# JBC_Station_V4.net
KiCad netlist of a schematic drawn in EAGLE
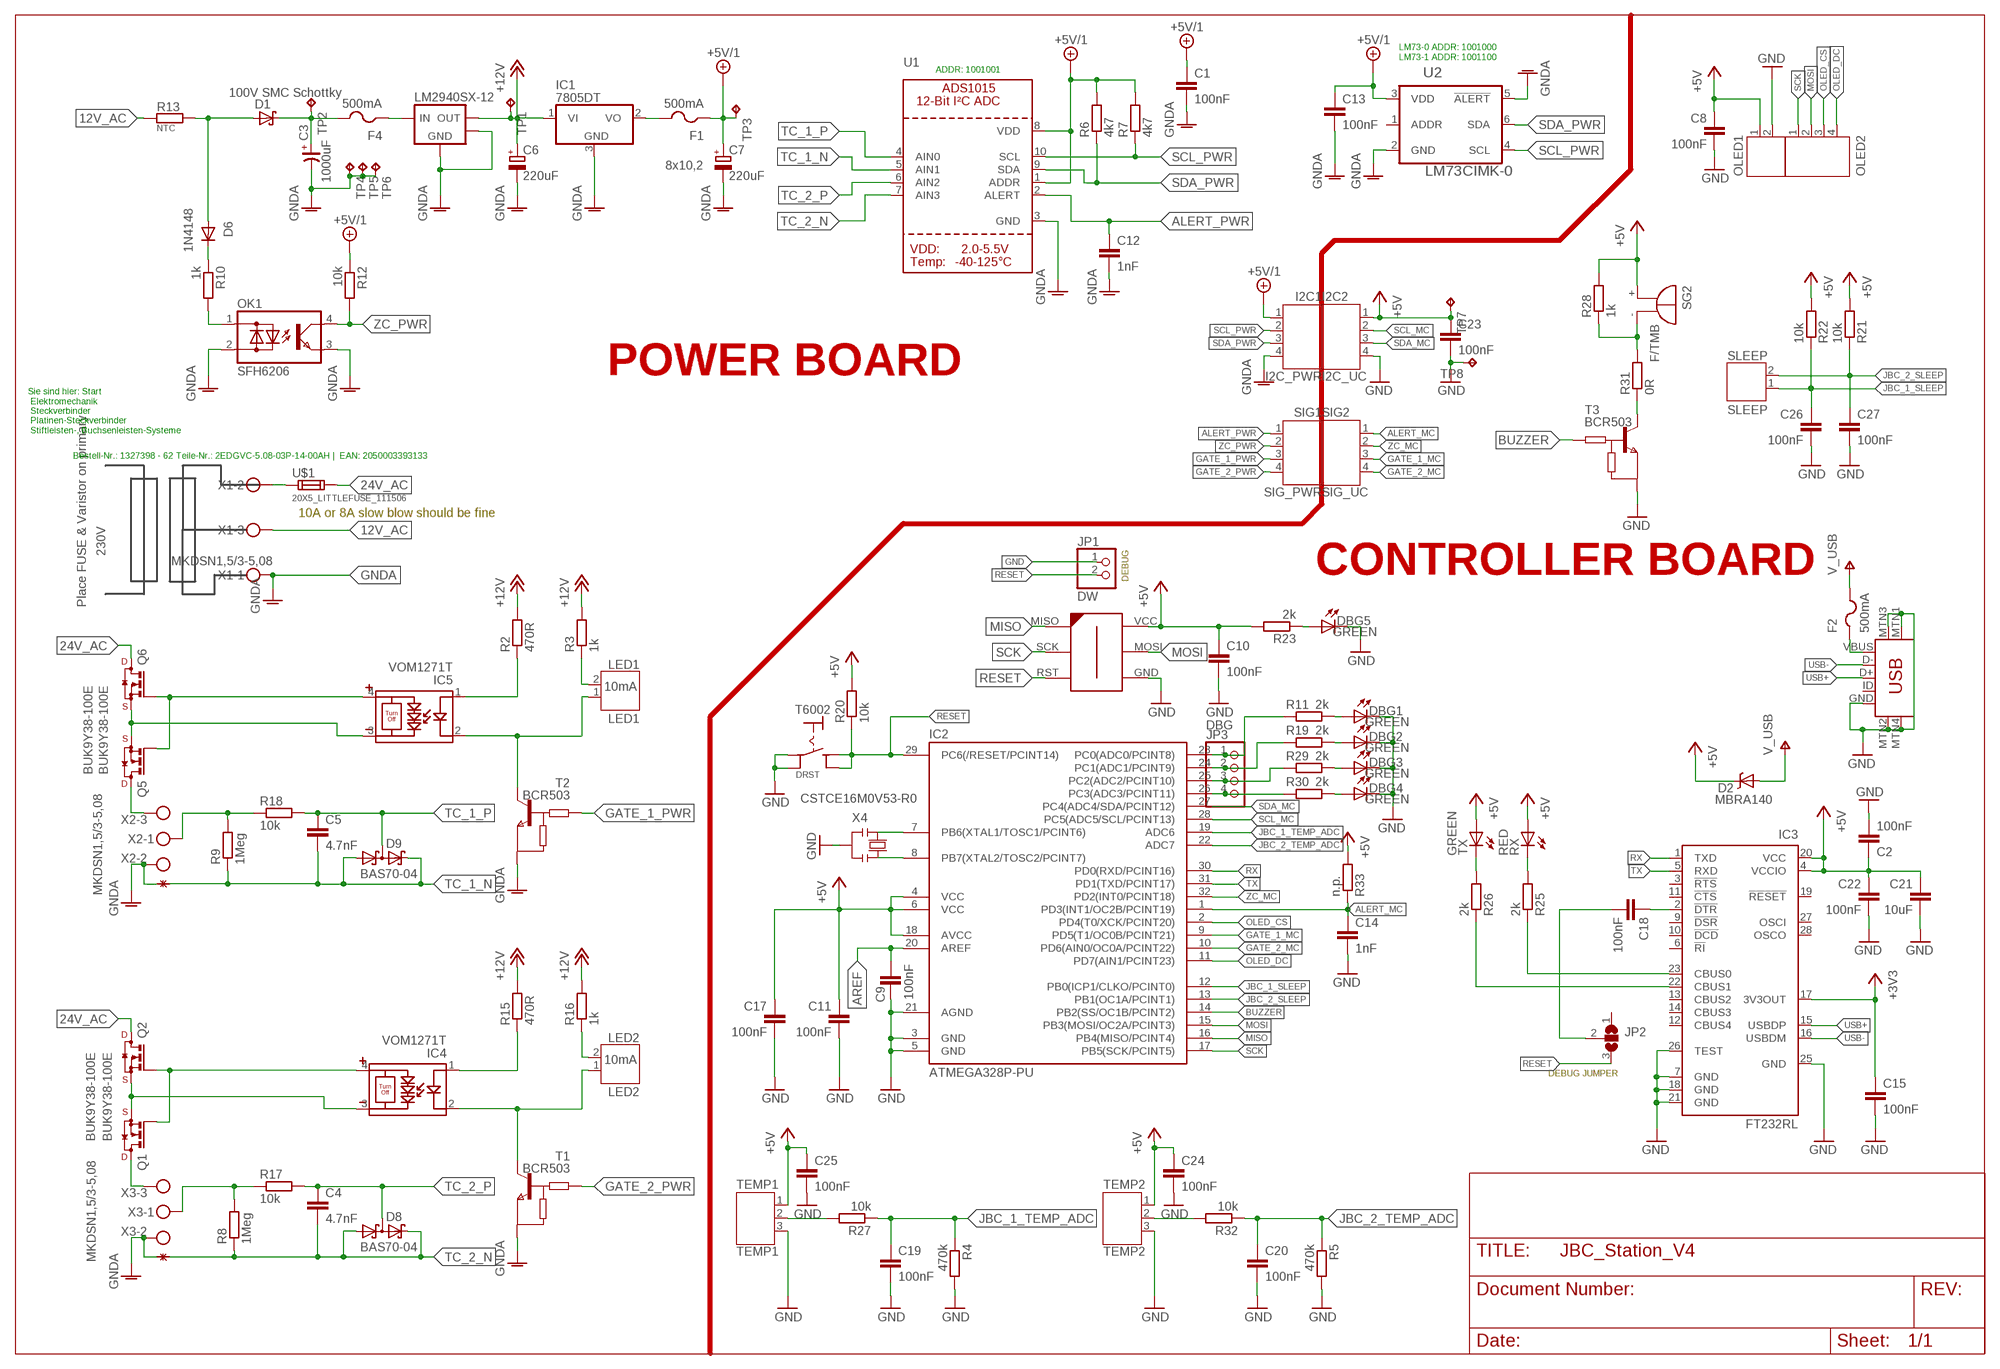
[diagram p0: schematic, sheet 1]

(export (version "E")
  (design (tool "Eeschema 10.0.6"))
  (components
    (comp (ref "C1")
      (value "100nF")
      (footprint "eagle-import:C0805")
      (libsource (lib "eagle-import") (part "C-EUC0805"))
    )
    (comp (ref "C2")
      (value "100nF")
      (footprint "eagle-import:C0805")
      (libsource (lib "eagle-import") (part "C-EUC0805"))
    )
    (comp (ref "C3")
      (value "1000uF")
      (footprint "eagle-import:CSV-H")
      (libsource (lib "eagle-import") (part "CP_SV-H"))
    )
    (comp (ref "C4")
      (value "4.7nF")
      (footprint "eagle-import:C0805")
      (libsource (lib "eagle-import") (part "C-EUC0805"))
    )
    (comp (ref "C5")
      (value "4.7nF")
      (footprint "eagle-import:C0805")
      (libsource (lib "eagle-import") (part "C-EUC0805"))
    )
    (comp (ref "C6")
      (value "220uF")
      (footprint "eagle-import:PANASONIC_E")
      (libsource (lib "eagle-import") (part "CPOL-EUE"))
    )
    (comp (ref "C7")
      (value "220uF")
      (footprint "eagle-import:PANASONIC_E")
      (libsource (lib "eagle-import") (part "CPOL-EUE"))
    )
    (comp (ref "C8")
      (value "100nF")
      (footprint "eagle-import:C0805")
      (libsource (lib "eagle-import") (part "C-EUC0805"))
    )
    (comp (ref "C9")
      (value "100nF")
      (footprint "eagle-import:C0805")
      (libsource (lib "eagle-import") (part "C-EUC0805"))
    )
    (comp (ref "C10")
      (value "100nF")
      (footprint "eagle-import:C0805")
      (libsource (lib "eagle-import") (part "C-EUC0805"))
    )
    (comp (ref "C11")
      (value "100nF")
      (footprint "eagle-import:C0805")
      (libsource (lib "eagle-import") (part "C-EUC0805"))
    )
    (comp (ref "C12")
      (value "1nF")
      (footprint "eagle-import:C0805")
      (libsource (lib "eagle-import") (part "C-EUC0805"))
    )
    (comp (ref "C13")
      (value "100nF")
      (footprint "eagle-import:C0805")
      (libsource (lib "eagle-import") (part "C-EUC0805"))
    )
    (comp (ref "C14")
      (value "1nF")
      (footprint "eagle-import:C0805")
      (libsource (lib "eagle-import") (part "C-EUC0805"))
    )
    (comp (ref "C15")
      (value "100nF")
      (footprint "eagle-import:C0805")
      (libsource (lib "eagle-import") (part "C-EUC0805"))
    )
    (comp (ref "C17")
      (value "100nF")
      (footprint "eagle-import:C0805")
      (libsource (lib "eagle-import") (part "C-EUC0805"))
    )
    (comp (ref "C18")
      (value "100nF")
      (footprint "eagle-import:C0805")
      (libsource (lib "eagle-import") (part "C-EUC0805"))
    )
    (comp (ref "C19")
      (value "100nF")
      (footprint "eagle-import:C0805")
      (libsource (lib "eagle-import") (part "C-EUC0805"))
    )
    (comp (ref "C20")
      (value "100nF")
      (footprint "eagle-import:C0805")
      (libsource (lib "eagle-import") (part "C-EUC0805"))
    )
    (comp (ref "C21")
      (value "10uF")
      (footprint "eagle-import:C1210")
      (libsource (lib "eagle-import") (part "C-EUC1210"))
    )
    (comp (ref "C22")
      (value "100nF")
      (footprint "eagle-import:C0805")
      (libsource (lib "eagle-import") (part "C-EUC0805"))
    )
    (comp (ref "C23")
      (value "100nF")
      (footprint "eagle-import:C0805")
      (libsource (lib "eagle-import") (part "C-EUC0805"))
    )
    (comp (ref "C24")
      (value "100nF")
      (footprint "eagle-import:C0805")
      (libsource (lib "eagle-import") (part "C-EUC0805"))
    )
    (comp (ref "C25")
      (value "100nF")
      (footprint "eagle-import:C0805")
      (libsource (lib "eagle-import") (part "C-EUC0805"))
    )
    (comp (ref "C26")
      (value "100nF")
      (footprint "eagle-import:C0805")
      (libsource (lib "eagle-import") (part "C-EUC0805"))
    )
    (comp (ref "C27")
      (value "100nF")
      (footprint "eagle-import:C0805")
      (libsource (lib "eagle-import") (part "C-EUC0805"))
    )
    (comp (ref "D1")
      (value "100V SMC Schottky")
      (footprint "eagle-import:SMC")
      (libsource (lib "eagle-import") (part "SCHOTTKY-DIODESMC"))
    )
    (comp (ref "D2")
      (value "MBRA140")
      (footprint "eagle-import:SMA-DIODE")
      (libsource (lib "eagle-import") (part "DIODE-SCHOTTKY_"))
    )
    (comp (ref "D6")
      (value "1N4148")
      (footprint "eagle-import:MINIMELF")
      (libsource (lib "eagle-import") (part "DIODE-MINIMELF"))
    )
    (comp (ref "D8")
      (value "BAS70-04")
      (footprint "eagle-import:SOT23")
      (libsource (lib "eagle-import") (part "BAS70-04"))
    )
    (comp (ref "D9")
      (value "BAS70-04")
      (footprint "eagle-import:SOT23")
      (libsource (lib "eagle-import") (part "BAS70-04"))
    )
    (comp (ref "DBG1")
      (value "GREEN")
      (footprint "eagle-import:CHIP-LED0603")
      (libsource (lib "eagle-import") (part "LEDCHIP-LED0603"))
    )
    (comp (ref "DBG2")
      (value "GREEN")
      (footprint "eagle-import:CHIP-LED0603")
      (libsource (lib "eagle-import") (part "LEDCHIP-LED0603"))
    )
    (comp (ref "DBG3")
      (value "GREEN")
      (footprint "eagle-import:CHIP-LED0603")
      (libsource (lib "eagle-import") (part "LEDCHIP-LED0603"))
    )
    (comp (ref "DBG4")
      (value "GREEN")
      (footprint "eagle-import:CHIP-LED0603")
      (libsource (lib "eagle-import") (part "LEDCHIP-LED0603"))
    )
    (comp (ref "DBG5")
      (value "GREEN")
      (footprint "eagle-import:CHIP-LED0603")
      (libsource (lib "eagle-import") (part "LEDCHIP-LED0603"))
    )
    (comp (ref "F1")
      (value "500mA")
      (footprint "eagle-import:R1206")
      (libsource (lib "eagle-import") (part "PTCFUSE-1206"))
    )
    (comp (ref "F2")
      (value "500mA")
      (footprint "eagle-import:R1206")
      (libsource (lib "eagle-import") (part "PTCFUSE-1206"))
    )
    (comp (ref "F4")
      (value "500mA")
      (footprint "eagle-import:R1206")
      (libsource (lib "eagle-import") (part "PTCFUSE-1206"))
    )
    (comp (ref "I2C1")
      (value "I2C_PWR")
      (footprint "eagle-import:JST-PH4")
      (libsource (lib "eagle-import") (part "JST-PH4"))
    )
    (comp (ref "I2C2")
      (value "I2C_UC")
      (footprint "eagle-import:JST-PH4")
      (libsource (lib "eagle-import") (part "JST-PH4"))
    )
    (comp (ref "IC1")
      (value "7805DT")
      (footprint "eagle-import:TO252")
      (libsource (lib "eagle-import") (part "78DT05"))
    )
    (comp (ref "IC2")
      (value "ATMEGA328P-PU")
      (footprint "eagle-import:TQFP32-08")
      (libsource (lib "eagle-import") (part "MEGA48/88/168-AU"))
    )
    (comp (ref "IC3")
      (value "FT232RL")
      (footprint "eagle-import:SSOP28")
      (libsource (lib "eagle-import") (part "FT232RL"))
    )
    (comp (ref "IC4")
      (value "VOM1271T")
      (footprint "eagle-import:SOP-4")
      (libsource (lib "eagle-import") (part "VOM1271T"))
    )
    (comp (ref "IC5")
      (value "VOM1271T")
      (footprint "eagle-import:SOP-4")
      (libsource (lib "eagle-import") (part "VOM1271T"))
    )
    (comp (ref "JP1")
      (value "DW")
      (footprint "eagle-import:1X02")
      (libsource (lib "eagle-import") (part "PINHD-1X2_2.54"))
    )
    (comp (ref "JP2")
      (value "SJ2W")
      (footprint "eagle-import:SJ_2")
      (libsource (lib "eagle-import") (part "SJ2W"))
    )
    (comp (ref "JP3")
      (value "DBG")
      (footprint "eagle-import:1X04_90")
      (libsource (lib "eagle-import") (part "PINHD-1X4/90"))
    )
    (comp (ref "LED1")
      (value "LED1")
      (footprint "eagle-import:JST-PH2")
      (libsource (lib "eagle-import") (part "JST-PH2"))
    )
    (comp (ref "LED2")
      (value "LED2")
      (footprint "eagle-import:JST-PH2")
      (libsource (lib "eagle-import") (part "JST-PH2"))
    )
    (comp (ref "LM2940SX-12")
      (value "LM2940KTT")
      (footprint "eagle-import:TO263-3")
      (libsource (lib "eagle-import") (part "LM2940KTT"))
    )
    (comp (ref "OK1")
      (value "SFH6206")
      (footprint "eagle-import:DIL4-SMD")
      (fields (field (name "MF") "VISHAY/TELEFUNKEN") (field (name "MPN") "SFH6206-3"))
      (libsource (lib "eagle-import") (part "SFH6206"))
    )
    (comp (ref "OLED1")
      (value "JST-PH2")
      (footprint "eagle-import:JST-PH2")
      (libsource (lib "eagle-import") (part "JST-PH2"))
    )
    (comp (ref "OLED2")
      (value "JST-PH4")
      (footprint "eagle-import:JST-PH4")
      (libsource (lib "eagle-import") (part "JST-PH4"))
    )
    (comp (ref "Q1")
      (value "BUK9Y38-100E")
      (footprint "eagle-import:SOT669-POWERPAK-SO-8L-SINGLE")
      (libsource (lib "eagle-import") (part "BUK9Y38-100E"))
    )
    (comp (ref "Q2")
      (value "BUK9Y38-100E")
      (footprint "eagle-import:SOT669-POWERPAK-SO-8L-SINGLE")
      (libsource (lib "eagle-import") (part "BUK9Y38-100E"))
    )
    (comp (ref "Q5")
      (value "BUK9Y38-100E")
      (footprint "eagle-import:SOT669-POWERPAK-SO-8L-SINGLE")
      (libsource (lib "eagle-import") (part "BUK9Y38-100E"))
    )
    (comp (ref "Q6")
      (value "BUK9Y38-100E")
      (footprint "eagle-import:SOT669-POWERPAK-SO-8L-SINGLE")
      (libsource (lib "eagle-import") (part "BUK9Y38-100E"))
    )
    (comp (ref "R2")
      (value "470R")
      (footprint "eagle-import:R0805")
      (libsource (lib "eagle-import") (part "R-EU_R0805"))
    )
    (comp (ref "R3")
      (value "1k")
      (footprint "eagle-import:R0805")
      (libsource (lib "eagle-import") (part "R-EU_R0805"))
    )
    (comp (ref "R4")
      (value "470k")
      (footprint "eagle-import:R0805")
      (libsource (lib "eagle-import") (part "R-EU_R0805"))
    )
    (comp (ref "R5")
      (value "470k")
      (footprint "eagle-import:R0805")
      (libsource (lib "eagle-import") (part "R-EU_R0805"))
    )
    (comp (ref "R6")
      (value "4k7")
      (footprint "eagle-import:R0805")
      (libsource (lib "eagle-import") (part "R-EU_R0805"))
    )
    (comp (ref "R7")
      (value "4k7")
      (footprint "eagle-import:R0805")
      (libsource (lib "eagle-import") (part "R-EU_R0805"))
    )
    (comp (ref "R8")
      (value "1Meg")
      (footprint "eagle-import:R0805")
      (libsource (lib "eagle-import") (part "R-EU_R0805"))
    )
    (comp (ref "R9")
      (value "1Meg")
      (footprint "eagle-import:R0805")
      (libsource (lib "eagle-import") (part "R-EU_R0805"))
    )
    (comp (ref "R10")
      (value "1k")
      (footprint "eagle-import:R0805")
      (libsource (lib "eagle-import") (part "R-EU_R0805"))
    )
    (comp (ref "R11")
      (value "2k")
      (footprint "eagle-import:R0805")
      (libsource (lib "eagle-import") (part "R-EU_R0805"))
    )
    (comp (ref "R12")
      (value "10k")
      (footprint "eagle-import:R0805")
      (libsource (lib "eagle-import") (part "R-EU_R0805"))
    )
    (comp (ref "R13")
      (value "NTC")
      (footprint "eagle-import:SQM-VERTICAL-7W")
      (libsource (lib "eagle-import") (part "SQMR7"))
    )
    (comp (ref "R15")
      (value "470R")
      (footprint "eagle-import:R0805")
      (libsource (lib "eagle-import") (part "R-EU_R0805"))
    )
    (comp (ref "R16")
      (value "1k")
      (footprint "eagle-import:R0805")
      (libsource (lib "eagle-import") (part "R-EU_R0805"))
    )
    (comp (ref "R17")
      (value "10k")
      (footprint "eagle-import:R0805")
      (libsource (lib "eagle-import") (part "R-EU_R0805"))
    )
    (comp (ref "R18")
      (value "10k")
      (footprint "eagle-import:R0805")
      (libsource (lib "eagle-import") (part "R-EU_R0805"))
    )
    (comp (ref "R19")
      (value "2k")
      (footprint "eagle-import:R0805")
      (libsource (lib "eagle-import") (part "R-EU_R0805"))
    )
    (comp (ref "R20")
      (value "10k")
      (footprint "eagle-import:R0805")
      (libsource (lib "eagle-import") (part "R-EU_R0805"))
    )
    (comp (ref "R21")
      (value "10k")
      (footprint "eagle-import:R0805")
      (libsource (lib "eagle-import") (part "R-EU_R0805"))
    )
    (comp (ref "R22")
      (value "10k")
      (footprint "eagle-import:R0805")
      (libsource (lib "eagle-import") (part "R-EU_R0805"))
    )
    (comp (ref "R23")
      (value "2k")
      (footprint "eagle-import:R0805")
      (libsource (lib "eagle-import") (part "R-EU_R0805"))
    )
    (comp (ref "R25")
      (value "2k")
      (footprint "eagle-import:R0805")
      (libsource (lib "eagle-import") (part "R-EU_R0805"))
    )
    (comp (ref "R26")
      (value "2k")
      (footprint "eagle-import:R0805")
      (libsource (lib "eagle-import") (part "R-EU_R0805"))
    )
    (comp (ref "R27")
      (value "10k")
      (footprint "eagle-import:R0805")
      (libsource (lib "eagle-import") (part "R-EU_R0805"))
    )
    (comp (ref "R28")
      (value "1k")
      (footprint "eagle-import:R0805")
      (libsource (lib "eagle-import") (part "R-EU_R0805"))
    )
    (comp (ref "R29")
      (value "2k")
      (footprint "eagle-import:R0805")
      (libsource (lib "eagle-import") (part "R-EU_R0805"))
    )
    (comp (ref "R30")
      (value "2k")
      (footprint "eagle-import:R0805")
      (libsource (lib "eagle-import") (part "R-EU_R0805"))
    )
    (comp (ref "R31")
      (value "0R")
      (footprint "eagle-import:R0805")
      (libsource (lib "eagle-import") (part "R-EU_R0805"))
    )
    (comp (ref "R32")
      (value "10k")
      (footprint "eagle-import:R0805")
      (libsource (lib "eagle-import") (part "R-EU_R0805"))
    )
    (comp (ref "R33")
      (value "n.p.")
      (footprint "eagle-import:R0805")
      (libsource (lib "eagle-import") (part "R-EU_R0805"))
    )
    (comp (ref "RX")
      (value "RED")
      (footprint "eagle-import:CHIP-LED0603")
      (libsource (lib "eagle-import") (part "LEDCHIP-LED0603"))
    )
    (comp (ref "SG2")
      (value "F/TMB")
      (footprint "eagle-import:F_TMB")
      (libsource (lib "eagle-import") (part "F/TMB"))
    )
    (comp (ref "SIG1")
      (value "SIG_PWR")
      (footprint "eagle-import:JST-PH4")
      (libsource (lib "eagle-import") (part "JST-PH4"))
    )
    (comp (ref "SIG2")
      (value "SIG_UC")
      (footprint "eagle-import:JST-PH4")
      (libsource (lib "eagle-import") (part "JST-PH4"))
    )
    (comp (ref "SLEEP")
      (value "SLEEP")
      (footprint "eagle-import:JST-PH2")
      (libsource (lib "eagle-import") (part "JST-PH2"))
    )
    (comp (ref "T1")
      (value "BCR503")
      (footprint "eagle-import:GM4_BIP_SOT23_RZ")
      (libsource (lib "eagle-import") (part "GM4_BIP_NPN-DIG_SOT23_RZ"))
    )
    (comp (ref "T2")
      (value "BCR503")
      (footprint "eagle-import:GM4_BIP_SOT23_RZ")
      (libsource (lib "eagle-import") (part "GM4_BIP_NPN-DIG_SOT23_RZ"))
    )
    (comp (ref "T3")
      (value "BCR503")
      (footprint "eagle-import:GM4_BIP_SOT23_RZ")
      (libsource (lib "eagle-import") (part "GM4_BIP_NPN-DIG_SOT23_RZ"))
    )
    (comp (ref "T6002")
      (value "DRST")
      (footprint "eagle-import:TASTE_DRST_TA1")
      (libsource (lib "eagle-import") (part "TASTE_DRST_TA1"))
    )
    (comp (ref "TEMP1")
      (value "TEMP1")
      (footprint "eagle-import:JST-PH3")
      (libsource (lib "eagle-import") (part "JST-PH3"))
    )
    (comp (ref "TEMP2")
      (value "TEMP2")
      (footprint "eagle-import:JST-PH3")
      (libsource (lib "eagle-import") (part "JST-PH3"))
    )
    (comp (ref "TP1")
      (value "TPTP17R")
      (footprint "eagle-import:TP17R")
      (libsource (lib "eagle-import") (part "TPTP17R"))
    )
    (comp (ref "TP2")
      (value "TPTP17R")
      (footprint "eagle-import:TP17R")
      (libsource (lib "eagle-import") (part "TPTP17R"))
    )
    (comp (ref "TP3")
      (value "TPTP17R")
      (footprint "eagle-import:TP17R")
      (libsource (lib "eagle-import") (part "TPTP17R"))
    )
    (comp (ref "TP4")
      (value "TPTP17R")
      (footprint "eagle-import:TP17R")
      (libsource (lib "eagle-import") (part "TPTP17R"))
    )
    (comp (ref "TP5")
      (value "TPTP17R")
      (footprint "eagle-import:TP17R")
      (libsource (lib "eagle-import") (part "TPTP17R"))
    )
    (comp (ref "TP6")
      (value "TPTP17R")
      (footprint "eagle-import:TP17R")
      (libsource (lib "eagle-import") (part "TPTP17R"))
    )
    (comp (ref "TP7")
      (value "TPTP17R")
      (footprint "eagle-import:TP17R")
      (libsource (lib "eagle-import") (part "TPTP17R"))
    )
    (comp (ref "TP8")
      (value "TPTP17R")
      (footprint "eagle-import:TP17R")
      (libsource (lib "eagle-import") (part "TPTP17R"))
    )
    (comp (ref "TX")
      (value "GREEN")
      (footprint "eagle-import:CHIP-LED0603")
      (libsource (lib "eagle-import") (part "LEDCHIP-LED0603"))
    )
    (comp (ref "U$1")
      (value "20X5_LITTLEFUSE_111506")
      (footprint "eagle-import:20X5_LITTLEFUSE_111506")
      (libsource (lib "eagle-import") (part "20X5_LITTLEFUSE_111506"))
    )
    (comp (ref "U$2")
      (value "STARPONT")
      (footprint "eagle-import:STARPOINT")
      (libsource (lib "eagle-import") (part "STARPONT"))
    )
    (comp (ref "U$3")
      (value "STARPONT")
      (footprint "eagle-import:STARPOINT")
      (libsource (lib "eagle-import") (part "STARPONT"))
    )
    (comp (ref "U$5")
      (value "AVR-ISP-6-EDGE")
      (footprint "eagle-import:6PAD_ISP")
      (libsource (lib "eagle-import") (part "AVR-ISP-6-EDGE"))
    )
    (comp (ref "U1")
      (value "ADC_ADS1015")
      (footprint "eagle-import:MSOP10")
      (libsource (lib "eagle-import") (part "ADC_ADS1015"))
    )
    (comp (ref "U2")
      (value "LM73CIMK-0")
      (footprint "eagle-import:SOT95P285X100-6N")
      (libsource (lib "eagle-import") (part "LM73CIMK-0"))
    )
    (comp (ref "USB")
      (value "USB-MINIB-5PIN")
      (footprint "eagle-import:USB-MINIB")
      (libsource (lib "eagle-import") (part "USB-MINIB-5PIN"))
    )
    (comp (ref "X1")
      (value "MKDSN1,5/3-5,08")
      (footprint "eagle-import:MKDSN1,5_3-5,08")
      (libsource (lib "eagle-import") (part "MKDSN1,5/3-5,08"))
    )
    (comp (ref "X2")
      (value "MKDSN1,5/3-5,08")
      (footprint "eagle-import:MKDSN1,5_3-5,08")
      (libsource (lib "eagle-import") (part "MKDSN1,5/3-5,08"))
    )
    (comp (ref "X3")
      (value "MKDSN1,5/3-5,08")
      (footprint "eagle-import:MKDSN1,5_3-5,08")
      (libsource (lib "eagle-import") (part "MKDSN1,5/3-5,08"))
    )
    (comp (ref "X4")
      (value "CSTCE16M0V53-R0")
      (footprint "eagle-import:RESONATOR")
      (libsource (lib "eagle-import") (part "0011_CSTCE16M0V53-R0"))
    )
  )
  (nets
    (net (code "1") (name "+3V3") (class "Default")
      (node (ref "C15") (pin "1") (pinfunction "1_1") (pintype "passive"))
      (node (ref "IC3") (pin "17") (pinfunction "3V3OUT_17") (pintype "output"))
    )
    (net (code "2") (name "+5V") (class "Default")
      (node (ref "C10") (pin "1") (pinfunction "1_1") (pintype "passive"))
      (node (ref "C11") (pin "1") (pinfunction "1_1") (pintype "passive"))
      (node (ref "C17") (pin "1") (pinfunction "1_1") (pintype "passive"))
      (node (ref "C2") (pin "1") (pinfunction "1_1") (pintype "passive"))
      (node (ref "C21") (pin "1") (pinfunction "1_1") (pintype "passive"))
      (node (ref "C22") (pin "1") (pinfunction "1_1") (pintype "passive"))
      (node (ref "C23") (pin "1") (pinfunction "1_1") (pintype "passive"))
      (node (ref "C24") (pin "1") (pinfunction "1_1") (pintype "passive"))
      (node (ref "C25") (pin "1") (pinfunction "1_1") (pintype "passive"))
      (node (ref "C8") (pin "1") (pinfunction "1_1") (pintype "passive"))
      (node (ref "D2") (pin "C") (pinfunction "C_C") (pintype "passive"))
      (node (ref "I2C2") (pin "1") (pinfunction "1_1") (pintype "passive"))
      (node (ref "IC2") (pin "18") (pinfunction "AVCC_18") (pintype "passive"))
      (node (ref "IC2") (pin "4") (pinfunction "VCC_4") (pintype "power_in"))
      (node (ref "IC2") (pin "6") (pinfunction "VCC_6") (pintype "power_in"))
      (node (ref "IC3") (pin "20") (pinfunction "VCC_20") (pintype "power_in"))
      (node (ref "IC3") (pin "4") (pinfunction "VCCIO_4") (pintype "power_in"))
      (node (ref "OLED1") (pin "1") (pinfunction "1_1") (pintype "passive"))
      (node (ref "R20") (pin "2") (pinfunction "2_2") (pintype "passive"))
      (node (ref "R21") (pin "2") (pinfunction "2_2") (pintype "passive"))
      (node (ref "R22") (pin "2") (pinfunction "2_2") (pintype "passive"))
      (node (ref "R23") (pin "2") (pinfunction "2_2") (pintype "passive"))
      (node (ref "R28") (pin "2") (pinfunction "2_2") (pintype "passive"))
      (node (ref "R33") (pin "2") (pinfunction "2_2") (pintype "passive"))
      (node (ref "RX") (pin "A") (pinfunction "A_A") (pintype "passive"))
      (node (ref "SG2") (pin "+") (pinfunction "+_+") (pintype "passive"))
      (node (ref "TEMP1") (pin "1") (pinfunction "1_1") (pintype "passive"))
      (node (ref "TEMP2") (pin "1") (pinfunction "1_1") (pintype "passive"))
      (node (ref "TP7") (pin "TP") (pinfunction "TP_TP") (pintype "input"))
      (node (ref "TX") (pin "A") (pinfunction "A_A") (pintype "passive"))
      (node (ref "U$5") (pin "VCC") (pinfunction "P$6_VCC") (pintype "bidirectional"))
    )
    (net (code "3") (name "+5V{slash}1") (class "Default")
      (node (ref "C1") (pin "1") (pinfunction "1_1") (pintype "passive"))
      (node (ref "C13") (pin "1") (pinfunction "1_1") (pintype "passive"))
      (node (ref "C7") (pin "+") (pinfunction "+_+") (pintype "passive"))
      (node (ref "F1") (pin "1") (pinfunction "1_1") (pintype "passive"))
      (node (ref "I2C1") (pin "1") (pinfunction "1_1") (pintype "passive"))
      (node (ref "R12") (pin "1") (pinfunction "1_1") (pintype "passive"))
      (node (ref "R6") (pin "2") (pinfunction "2_2") (pintype "passive"))
      (node (ref "R7") (pin "2") (pinfunction "2_2") (pintype "passive"))
      (node (ref "TP3") (pin "TP") (pinfunction "TP_TP") (pintype "input"))
      (node (ref "U1") (pin "1") (pinfunction "ADDR_1") (pintype "bidirectional"))
      (node (ref "U1") (pin "8") (pinfunction "VDD_8") (pintype "bidirectional"))
      (node (ref "U2") (pin "3") (pinfunction "VDD_3") (pintype "power_in"))
    )
    (net (code "4") (name "+12V") (class "Default")
      (node (ref "C6") (pin "+") (pinfunction "+_+") (pintype "passive"))
      (node (ref "IC1") (pin "1") (pinfunction "VI_1") (pintype "input"))
      (node (ref "LM2940SX-12") (pin "3") (pinfunction "VOUT_3") (pintype "power_in"))
      (node (ref "R15") (pin "2") (pinfunction "2_2") (pintype "passive"))
      (node (ref "R16") (pin "2") (pinfunction "2_2") (pintype "passive"))
      (node (ref "R2") (pin "2") (pinfunction "2_2") (pintype "passive"))
      (node (ref "R3") (pin "2") (pinfunction "2_2") (pintype "passive"))
      (node (ref "TP1") (pin "TP") (pinfunction "TP_TP") (pintype "input"))
    )
    (net (code "5") (name "12V_AC") (class "Default")
      (node (ref "R13") (pin "P$1") (pinfunction "1_P$1") (pintype "passive"))
      (node (ref "X1") (pin "3") (pinfunction "KL_3") (pintype "passive"))
    )
    (net (code "6") (name "24V_AC") (class "Default")
      (node (ref "Q2") (pin "5") (pinfunction "D_5") (pintype "passive"))
      (node (ref "Q6") (pin "5") (pinfunction "D_5") (pintype "passive"))
      (node (ref "U$1") (pin "21") (pinfunction "2_21") (pintype "passive"))
      (node (ref "U$1") (pin "22") (pinfunction "2_22") (pintype "passive"))
    )
    (net (code "7") (name "ALERT_MC") (class "Default")
      (node (ref "C14") (pin "1") (pinfunction "1_1") (pintype "passive"))
      (node (ref "IC2") (pin "1") (pinfunction "PD3(INT1/OC2B/PCINT19)_1") (pintype "bidirectional"))
      (node (ref "R33") (pin "1") (pinfunction "1_1") (pintype "passive"))
      (node (ref "SIG2") (pin "1") (pinfunction "1_1") (pintype "passive"))
    )
    (net (code "8") (name "ALERT_PWR") (class "Default")
      (node (ref "C12") (pin "1") (pinfunction "1_1") (pintype "passive"))
      (node (ref "SIG1") (pin "1") (pinfunction "1_1") (pintype "passive"))
      (node (ref "U1") (pin "2") (pinfunction "ALERT_2") (pintype "bidirectional"))
    )
    (net (code "9") (name "AREF") (class "Default")
      (node (ref "C9") (pin "1") (pinfunction "1_1") (pintype "passive"))
      (node (ref "IC2") (pin "20") (pinfunction "AREF_20") (pintype "passive"))
    )
    (net (code "10") (name "BUZZER") (class "Default")
      (node (ref "IC2") (pin "14") (pinfunction "PB2(SS/OC1B/PCINT2)_14") (pintype "bidirectional"))
      (node (ref "T3") (pin "1") (pinfunction "B_1") (pintype "passive"))
    )
    (net (code "11") (name "GATE_1_MC") (class "Default")
      (node (ref "IC2") (pin "9") (pinfunction "PD5(T1/OC0B/PCINT21)_9") (pintype "bidirectional"))
      (node (ref "SIG2") (pin "3") (pinfunction "3_3") (pintype "passive"))
    )
    (net (code "12") (name "GATE_1_PWR") (class "Default")
      (node (ref "SIG1") (pin "3") (pinfunction "3_3") (pintype "passive"))
      (node (ref "T2") (pin "1") (pinfunction "B_1") (pintype "passive"))
    )
    (net (code "13") (name "GATE_2_MC") (class "Default")
      (node (ref "IC2") (pin "10") (pinfunction "PD6(AIN0/OC0A/PCINT22)_10") (pintype "bidirectional"))
      (node (ref "SIG2") (pin "4") (pinfunction "4_4") (pintype "passive"))
    )
    (net (code "14") (name "GATE_2_PWR") (class "Default")
      (node (ref "SIG1") (pin "4") (pinfunction "4_4") (pintype "passive"))
      (node (ref "T1") (pin "1") (pinfunction "B_1") (pintype "passive"))
    )
    (net (code "15") (name "GND") (class "Default")
      (node (ref "C10") (pin "2") (pinfunction "2_2") (pintype "passive"))
      (node (ref "C11") (pin "2") (pinfunction "2_2") (pintype "passive"))
      (node (ref "C14") (pin "2") (pinfunction "2_2") (pintype "passive"))
      (node (ref "C15") (pin "2") (pinfunction "2_2") (pintype "passive"))
      (node (ref "C17") (pin "2") (pinfunction "2_2") (pintype "passive"))
      (node (ref "C19") (pin "2") (pinfunction "2_2") (pintype "passive"))
      (node (ref "C2") (pin "2") (pinfunction "2_2") (pintype "passive"))
      (node (ref "C20") (pin "2") (pinfunction "2_2") (pintype "passive"))
      (node (ref "C21") (pin "2") (pinfunction "2_2") (pintype "passive"))
      (node (ref "C22") (pin "2") (pinfunction "2_2") (pintype "passive"))
      (node (ref "C23") (pin "2") (pinfunction "2_2") (pintype "passive"))
      (node (ref "C24") (pin "2") (pinfunction "2_2") (pintype "passive"))
      (node (ref "C25") (pin "2") (pinfunction "2_2") (pintype "passive"))
      (node (ref "C26") (pin "2") (pinfunction "2_2") (pintype "passive"))
      (node (ref "C27") (pin "2") (pinfunction "2_2") (pintype "passive"))
      (node (ref "C8") (pin "2") (pinfunction "2_2") (pintype "passive"))
      (node (ref "C9") (pin "2") (pinfunction "2_2") (pintype "passive"))
      (node (ref "DBG1") (pin "C") (pinfunction "C_C") (pintype "passive"))
      (node (ref "DBG2") (pin "C") (pinfunction "C_C") (pintype "passive"))
      (node (ref "DBG3") (pin "C") (pinfunction "C_C") (pintype "passive"))
      (node (ref "DBG4") (pin "C") (pinfunction "C_C") (pintype "passive"))
      (node (ref "DBG5") (pin "C") (pinfunction "C_C") (pintype "passive"))
      (node (ref "I2C2") (pin "4") (pinfunction "4_4") (pintype "passive"))
      (node (ref "IC2") (pin "21") (pinfunction "AGND_21") (pintype "power_in"))
      (node (ref "IC2") (pin "3") (pinfunction "GND_3") (pintype "power_in"))
      (node (ref "IC2") (pin "5") (pinfunction "GND_5") (pintype "power_in"))
      (node (ref "IC3") (pin "18") (pinfunction "GND_18") (pintype "power_in"))
      (node (ref "IC3") (pin "21") (pinfunction "GND_21") (pintype "power_in"))
      (node (ref "IC3") (pin "25") (pinfunction "GND_25") (pintype "power_in"))
      (node (ref "IC3") (pin "26") (pinfunction "TEST_26") (pintype "input"))
      (node (ref "IC3") (pin "7") (pinfunction "GND_7") (pintype "power_in"))
      (node (ref "JP1") (pin "1") (pinfunction "1_1") (pintype "passive"))
      (node (ref "OLED1") (pin "2") (pinfunction "2_2") (pintype "passive"))
      (node (ref "R4") (pin "2") (pinfunction "2_2") (pintype "passive"))
      (node (ref "R5") (pin "2") (pinfunction "2_2") (pintype "passive"))
      (node (ref "T3") (pin "2") (pinfunction "E_2") (pintype "passive"))
      (node (ref "T6002") (pin "P$1") (pinfunction "1_P$1") (pintype "passive"))
      (node (ref "T6002") (pin "P$2") (pinfunction "1_P$2") (pintype "passive"))
      (node (ref "TEMP1") (pin "3") (pinfunction "3_3") (pintype "passive"))
      (node (ref "TEMP2") (pin "3") (pinfunction "3_3") (pintype "passive"))
      (node (ref "TP8") (pin "TP") (pinfunction "TP_TP") (pintype "input"))
      (node (ref "U$5") (pin "GND") (pinfunction "P$4_GND") (pintype "bidirectional"))
      (node (ref "USB") (pin "GND") (pinfunction "GND_GND") (pintype "bidirectional"))
      (node (ref "USB") (pin "MTN1") (pinfunction "MTN2_MTN1") (pintype "bidirectional"))
      (node (ref "USB") (pin "MTN2") (pinfunction "MTN3_MTN2") (pintype "bidirectional"))
      (node (ref "USB") (pin "MTN3") (pinfunction "MTN1_MTN3") (pintype "bidirectional"))
      (node (ref "USB") (pin "MTN4") (pinfunction "MTN4_MTN4") (pintype "bidirectional"))
      (node (ref "X4") (pin "2") (pinfunction "2_2") (pintype "passive"))
    )
    (net (code "16") (name "GNDA") (class "Default")
      (node (ref "C1") (pin "2") (pinfunction "2_2") (pintype "passive"))
      (node (ref "C12") (pin "2") (pinfunction "2_2") (pintype "passive"))
      (node (ref "C13") (pin "2") (pinfunction "2_2") (pintype "passive"))
      (node (ref "C3") (pin "-") (pinfunction "-_-") (pintype "passive"))
      (node (ref "C6") (pin "-") (pinfunction "-_-") (pintype "passive"))
      (node (ref "C7") (pin "-") (pinfunction "-_-") (pintype "passive"))
      (node (ref "I2C1") (pin "4") (pinfunction "4_4") (pintype "passive"))
      (node (ref "IC1") (pin "3") (pinfunction "GND_3") (pintype "passive"))
      (node (ref "LM2940SX-12") (pin "2") (pinfunction "GND_2") (pintype "power_in"))
      (node (ref "LM2940SX-12") (pin "TAB") (pinfunction "TAB_TAB") (pintype "power_in"))
      (node (ref "OK1") (pin "2") (pinfunction "AC2_2") (pintype "passive"))
      (node (ref "OK1") (pin "3") (pinfunction "E_3") (pintype "passive"))
      (node (ref "T1") (pin "2") (pinfunction "E_2") (pintype "passive"))
      (node (ref "T2") (pin "2") (pinfunction "E_2") (pintype "passive"))
      (node (ref "TP4") (pin "TP") (pinfunction "TP_TP") (pintype "input"))
      (node (ref "TP5") (pin "TP") (pinfunction "TP_TP") (pintype "input"))
      (node (ref "TP6") (pin "TP") (pinfunction "TP_TP") (pintype "input"))
      (node (ref "U$2") (pin "P$2") (pinfunction "P$2_P$2") (pintype "bidirectional"))
      (node (ref "U$3") (pin "P$2") (pinfunction "P$2_P$2") (pintype "bidirectional"))
      (node (ref "U1") (pin "3") (pinfunction "GND_3") (pintype "bidirectional"))
      (node (ref "U2") (pin "2") (pinfunction "GND_2") (pintype "passive"))
      (node (ref "U2") (pin "5") (pinfunction "~{ALERT}_5") (pintype "output"))
      (node (ref "X1") (pin "1") (pinfunction "KL_1") (pintype "passive"))
      (node (ref "X2") (pin "2") (pinfunction "KL_2") (pintype "passive"))
      (node (ref "X3") (pin "2") (pinfunction "KL_2") (pintype "passive"))
    )
    (net (code "17") (name "JBC_1_SLEEP") (class "Default")
      (node (ref "C26") (pin "1") (pinfunction "1_1") (pintype "passive"))
      (node (ref "IC2") (pin "12") (pinfunction "PB0(ICP1/CLKO/PCINT0)_12") (pintype "bidirectional"))
      (node (ref "R22") (pin "1") (pinfunction "1_1") (pintype "passive"))
      (node (ref "SLEEP") (pin "1") (pinfunction "1_1") (pintype "passive"))
    )
    (net (code "18") (name "JBC_1_TEMP_ADC") (class "Default")
      (node (ref "C19") (pin "1") (pinfunction "1_1") (pintype "passive"))
      (node (ref "IC2") (pin "19") (pinfunction "ADC6_19") (pintype "passive"))
      (node (ref "R27") (pin "1") (pinfunction "1_1") (pintype "passive"))
      (node (ref "R4") (pin "1") (pinfunction "1_1") (pintype "passive"))
    )
    (net (code "19") (name "JBC_2_SLEEP") (class "Default")
      (node (ref "C27") (pin "1") (pinfunction "1_1") (pintype "passive"))
      (node (ref "IC2") (pin "13") (pinfunction "PB1(OC1A/PCINT1)_13") (pintype "bidirectional"))
      (node (ref "R21") (pin "1") (pinfunction "1_1") (pintype "passive"))
      (node (ref "SLEEP") (pin "2") (pinfunction "2_2") (pintype "passive"))
    )
    (net (code "20") (name "JBC_2_TEMP_ADC") (class "Default")
      (node (ref "C20") (pin "1") (pinfunction "1_1") (pintype "passive"))
      (node (ref "IC2") (pin "22") (pinfunction "ADC7_22") (pintype "passive"))
      (node (ref "R32") (pin "1") (pinfunction "1_1") (pintype "passive"))
      (node (ref "R5") (pin "1") (pinfunction "1_1") (pintype "passive"))
    )
    (net (code "21") (name "MISO") (class "Default")
      (node (ref "IC2") (pin "16") (pinfunction "PB4(MISO/PCINT4)_16") (pintype "bidirectional"))
      (node (ref "U$5") (pin "MISO") (pinfunction "P$1_MISO") (pintype "bidirectional"))
    )
    (net (code "22") (name "MOSI") (class "Default")
      (node (ref "IC2") (pin "15") (pinfunction "PB3(MOSI/OC2A/PCINT3)_15") (pintype "bidirectional"))
      (node (ref "OLED2") (pin "2") (pinfunction "2_2") (pintype "passive"))
      (node (ref "U$5") (pin "MOSI") (pinfunction "P$5_MOSI") (pintype "bidirectional"))
    )
    (net (code "23") (name "Net-(C3-Pad+)") (class "Default")
      (node (ref "C3") (pin "+") (pinfunction "+_+") (pintype "passive"))
      (node (ref "D1") (pin "C") (pinfunction "C_C") (pintype "passive"))
      (node (ref "F4") (pin "2") (pinfunction "2_2") (pintype "passive"))
      (node (ref "TP2") (pin "TP") (pinfunction "TP_TP") (pintype "input"))
    )
    (net (code "24") (name "Net-(C18-Pad2)") (class "Default")
      (node (ref "C18") (pin "2") (pinfunction "2_2") (pintype "passive"))
      (node (ref "JP2") (pin "2") (pinfunction "2_2") (pintype "passive"))
    )
    (net (code "25") (name "Net-(D6-PadC)") (class "Default")
      (node (ref "D6") (pin "C") (pinfunction "C_C") (pintype "passive"))
      (node (ref "R10") (pin "1") (pinfunction "1_1") (pintype "passive"))
    )
    (net (code "26") (name "Net-(DBG1-PadA)") (class "Default")
      (node (ref "DBG1") (pin "A") (pinfunction "A_A") (pintype "passive"))
      (node (ref "R11") (pin "1") (pinfunction "1_1") (pintype "passive"))
    )
    (net (code "27") (name "Net-(DBG2-PadA)") (class "Default")
      (node (ref "DBG2") (pin "A") (pinfunction "A_A") (pintype "passive"))
      (node (ref "R19") (pin "1") (pinfunction "1_1") (pintype "passive"))
    )
    (net (code "28") (name "Net-(DBG3-PadA)") (class "Default")
      (node (ref "DBG3") (pin "A") (pinfunction "A_A") (pintype "passive"))
      (node (ref "R29") (pin "1") (pinfunction "1_1") (pintype "passive"))
    )
    (net (code "29") (name "Net-(DBG4-PadA)") (class "Default")
      (node (ref "DBG4") (pin "A") (pinfunction "A_A") (pintype "passive"))
      (node (ref "R30") (pin "1") (pinfunction "1_1") (pintype "passive"))
    )
    (net (code "30") (name "Net-(DBG5-PadA)") (class "Default")
      (node (ref "DBG5") (pin "A") (pinfunction "A_A") (pintype "passive"))
      (node (ref "R23") (pin "1") (pinfunction "1_1") (pintype "passive"))
    )
    (net (code "31") (name "Net-(F2-Pad1)") (class "Default")
      (node (ref "F2") (pin "1") (pinfunction "1_1") (pintype "passive"))
      (node (ref "USB") (pin "VBUS") (pinfunction "VBUS_VBUS") (pintype "bidirectional"))
    )
    (net (code "32") (name "Net-(IC1-VO)") (class "Default")
      (node (ref "F1") (pin "2") (pinfunction "2_2") (pintype "passive"))
      (node (ref "IC1") (pin "2") (pinfunction "VO_2") (pintype "passive"))
    )
    (net (code "33") (name "Net-(IC2-PB6(XTAL1{slash}TOSC1{slash}PCINT6))") (class "Default")
      (node (ref "IC2") (pin "7") (pinfunction "PB6(XTAL1/TOSC1/PCINT6)_7") (pintype "bidirectional"))
      (node (ref "X4") (pin "1") (pinfunction "1_1") (pintype "passive"))
    )
    (net (code "34") (name "Net-(IC2-PB7(XTAL2{slash}TOSC2{slash}PCINT7))") (class "Default")
      (node (ref "IC2") (pin "8") (pinfunction "PB7(XTAL2/TOSC2/PCINT7)_8") (pintype "bidirectional"))
      (node (ref "X4") (pin "3") (pinfunction "3_3") (pintype "passive"))
    )
    (net (code "35") (name "Net-(IC2-PC0(ADC0{slash}PCINT8))") (class "Default")
      (node (ref "IC2") (pin "23") (pinfunction "PC0(ADC0/PCINT8)_23") (pintype "bidirectional"))
      (node (ref "JP3") (pin "1") (pinfunction "1_1") (pintype "passive"))
      (node (ref "R11") (pin "2") (pinfunction "2_2") (pintype "passive"))
    )
    (net (code "36") (name "Net-(IC2-PC1(ADC1{slash}PCINT9))") (class "Default")
      (node (ref "IC2") (pin "24") (pinfunction "PC1(ADC1/PCINT9)_24") (pintype "bidirectional"))
      (node (ref "JP3") (pin "2") (pinfunction "2_2") (pintype "passive"))
      (node (ref "R19") (pin "2") (pinfunction "2_2") (pintype "passive"))
    )
    (net (code "37") (name "Net-(IC2-PC2(ADC2{slash}PCINT10))") (class "Default")
      (node (ref "IC2") (pin "25") (pinfunction "PC2(ADC2/PCINT10)_25") (pintype "bidirectional"))
      (node (ref "JP3") (pin "3") (pinfunction "3_3") (pintype "passive"))
      (node (ref "R29") (pin "2") (pinfunction "2_2") (pintype "passive"))
    )
    (net (code "38") (name "Net-(IC2-PC3(ADC3{slash}PCINT11))") (class "Default")
      (node (ref "IC2") (pin "26") (pinfunction "PC3(ADC3/PCINT11)_26") (pintype "bidirectional"))
      (node (ref "JP3") (pin "4") (pinfunction "4_4") (pintype "passive"))
      (node (ref "R30") (pin "2") (pinfunction "2_2") (pintype "passive"))
    )
    (net (code "39") (name "Net-(IC3-CBUS0)") (class "Default")
      (node (ref "IC3") (pin "23") (pinfunction "CBUS0_23") (pintype "bidirectional"))
      (node (ref "R25") (pin "1") (pinfunction "1_1") (pintype "passive"))
    )
    (net (code "40") (name "Net-(IC3-CBUS1)") (class "Default")
      (node (ref "IC3") (pin "22") (pinfunction "CBUS1_22") (pintype "bidirectional"))
      (node (ref "R26") (pin "1") (pinfunction "1_1") (pintype "passive"))
    )
    (net (code "41") (name "Net-(IC3-~{DTR})") (class "Default")
      (node (ref "C18") (pin "1") (pinfunction "1_1") (pintype "passive"))
      (node (ref "IC3") (pin "2") (pinfunction "~{DTR}_2") (pintype "output"))
    )
    (net (code "42") (name "Net-(IC4-P$1)") (class "Default")
      (node (ref "IC4") (pin "1") (pinfunction "P$1_1") (pintype "bidirectional"))
      (node (ref "R15") (pin "1") (pinfunction "1_1") (pintype "passive"))
    )
    (net (code "43") (name "Net-(IC4-P$2)") (class "Default")
      (node (ref "IC4") (pin "2") (pinfunction "P$2_2") (pintype "bidirectional"))
      (node (ref "LED2") (pin "1") (pinfunction "1_1") (pintype "passive"))
      (node (ref "T1") (pin "3") (pinfunction "C_3") (pintype "passive"))
    )
    (net (code "44") (name "Net-(IC4-P$3)") (class "Default")
      (node (ref "IC4") (pin "3") (pinfunction "P$3_3") (pintype "bidirectional"))
      (node (ref "Q1") (pin "1") (pinfunction "S_1") (pintype "passive"))
      (node (ref "Q1") (pin "2") (pinfunction "S_2") (pintype "passive"))
      (node (ref "Q1") (pin "3") (pinfunction "S_3") (pintype "passive"))
      (node (ref "Q2") (pin "1") (pinfunction "S_1") (pintype "passive"))
      (node (ref "Q2") (pin "2") (pinfunction "S_2") (pintype "passive"))
      (node (ref "Q2") (pin "3") (pinfunction "S_3") (pintype "passive"))
    )
    (net (code "45") (name "Net-(IC4-P$4)") (class "Default")
      (node (ref "IC4") (pin "4") (pinfunction "P$4_4") (pintype "bidirectional"))
      (node (ref "Q1") (pin "4") (pinfunction "G_4") (pintype "passive"))
      (node (ref "Q2") (pin "4") (pinfunction "G_4") (pintype "passive"))
    )
    (net (code "46") (name "Net-(IC5-P$1)") (class "Default")
      (node (ref "IC5") (pin "1") (pinfunction "P$1_1") (pintype "bidirectional"))
      (node (ref "R2") (pin "1") (pinfunction "1_1") (pintype "passive"))
    )
    (net (code "47") (name "Net-(IC5-P$2)") (class "Default")
      (node (ref "IC5") (pin "2") (pinfunction "P$2_2") (pintype "bidirectional"))
      (node (ref "LED1") (pin "1") (pinfunction "1_1") (pintype "passive"))
      (node (ref "T2") (pin "3") (pinfunction "C_3") (pintype "passive"))
    )
    (net (code "48") (name "Net-(IC5-P$3)") (class "Default")
      (node (ref "IC5") (pin "3") (pinfunction "P$3_3") (pintype "bidirectional"))
      (node (ref "Q5") (pin "1") (pinfunction "S_1") (pintype "passive"))
      (node (ref "Q5") (pin "2") (pinfunction "S_2") (pintype "passive"))
      (node (ref "Q5") (pin "3") (pinfunction "S_3") (pintype "passive"))
      (node (ref "Q6") (pin "1") (pinfunction "S_1") (pintype "passive"))
      (node (ref "Q6") (pin "2") (pinfunction "S_2") (pintype "passive"))
      (node (ref "Q6") (pin "3") (pinfunction "S_3") (pintype "passive"))
    )
    (net (code "49") (name "Net-(IC5-P$4)") (class "Default")
      (node (ref "IC5") (pin "4") (pinfunction "P$4_4") (pintype "bidirectional"))
      (node (ref "Q5") (pin "4") (pinfunction "G_4") (pintype "passive"))
      (node (ref "Q6") (pin "4") (pinfunction "G_4") (pintype "passive"))
    )
    (net (code "50") (name "Net-(LED1-Pad2)") (class "Default")
      (node (ref "LED1") (pin "2") (pinfunction "2_2") (pintype "passive"))
      (node (ref "R3") (pin "1") (pinfunction "1_1") (pintype "passive"))
    )
    (net (code "51") (name "Net-(LED2-Pad2)") (class "Default")
      (node (ref "LED2") (pin "2") (pinfunction "2_2") (pintype "passive"))
      (node (ref "R16") (pin "1") (pinfunction "1_1") (pintype "passive"))
    )
    (net (code "52") (name "Net-(LM2940SX-12-VIN)") (class "Default")
      (node (ref "F4") (pin "1") (pinfunction "1_1") (pintype "passive"))
      (node (ref "LM2940SX-12") (pin "1") (pinfunction "VIN_1") (pintype "power_in"))
    )
    (net (code "53") (name "Net-(OK1-AC1)") (class "Default")
      (node (ref "OK1") (pin "1") (pinfunction "AC1_1") (pintype "passive"))
      (node (ref "R10") (pin "2") (pinfunction "2_2") (pintype "passive"))
    )
    (net (code "54") (name "Net-(Q1-D)") (class "Default")
      (node (ref "Q1") (pin "5") (pinfunction "D_5") (pintype "passive"))
      (node (ref "X3") (pin "3") (pinfunction "KL_3") (pintype "passive"))
    )
    (net (code "55") (name "Net-(Q5-D)") (class "Default")
      (node (ref "Q5") (pin "5") (pinfunction "D_5") (pintype "passive"))
      (node (ref "X2") (pin "3") (pinfunction "KL_3") (pintype "passive"))
    )
    (net (code "56") (name "Net-(R13-2)") (class "Default")
      (node (ref "D1") (pin "A") (pinfunction "A_A") (pintype "passive"))
      (node (ref "D6") (pin "A") (pinfunction "A_A") (pintype "passive"))
      (node (ref "R13") (pin "P$2") (pinfunction "2_P$2") (pintype "passive"))
    )
    (net (code "57") (name "Net-(R25-Pad2)") (class "Default")
      (node (ref "R25") (pin "2") (pinfunction "2_2") (pintype "passive"))
      (node (ref "RX") (pin "C") (pinfunction "C_C") (pintype "passive"))
    )
    (net (code "58") (name "Net-(R26-Pad2)") (class "Default")
      (node (ref "R26") (pin "2") (pinfunction "2_2") (pintype "passive"))
      (node (ref "TX") (pin "C") (pinfunction "C_C") (pintype "passive"))
    )
    (net (code "59") (name "Net-(R27-Pad2)") (class "Default")
      (node (ref "R27") (pin "2") (pinfunction "2_2") (pintype "passive"))
      (node (ref "TEMP1") (pin "2") (pinfunction "2_2") (pintype "passive"))
    )
    (net (code "60") (name "Net-(R28-Pad1)") (class "Default")
      (node (ref "R28") (pin "1") (pinfunction "1_1") (pintype "passive"))
      (node (ref "R31") (pin "2") (pinfunction "2_2") (pintype "passive"))
      (node (ref "SG2") (pin "-") (pinfunction "-_-") (pintype "passive"))
    )
    (net (code "61") (name "Net-(R32-Pad2)") (class "Default")
      (node (ref "R32") (pin "2") (pinfunction "2_2") (pintype "passive"))
      (node (ref "TEMP2") (pin "2") (pinfunction "2_2") (pintype "passive"))
    )
    (net (code "62") (name "Net-(T3-C)") (class "Default")
      (node (ref "R31") (pin "1") (pinfunction "1_1") (pintype "passive"))
      (node (ref "T3") (pin "3") (pinfunction "C_3") (pintype "passive"))
    )
    (net (code "63") (name "Net-(X1B-KL)") (class "Default")
      (node (ref "U$1") (pin "11") (pinfunction "1_11") (pintype "passive"))
      (node (ref "U$1") (pin "12") (pinfunction "1_12") (pintype "passive"))
      (node (ref "X1") (pin "2") (pinfunction "KL_2") (pintype "passive"))
    )
    (net (code "64") (name "Net-(X2A-KL)") (class "Default")
      (node (ref "R18") (pin "1") (pinfunction "1_1") (pintype "passive"))
      (node (ref "R9") (pin "2") (pinfunction "2_2") (pintype "passive"))
      (node (ref "X2") (pin "1") (pinfunction "KL_1") (pintype "passive"))
    )
    (net (code "65") (name "Net-(X3A-KL)") (class "Default")
      (node (ref "R17") (pin "1") (pinfunction "1_1") (pintype "passive"))
      (node (ref "R8") (pin "2") (pinfunction "2_2") (pintype "passive"))
      (node (ref "X3") (pin "1") (pinfunction "KL_1") (pintype "passive"))
    )
    (net (code "66") (name "OLED_CS") (class "Default")
      (node (ref "IC2") (pin "2") (pinfunction "PD4(T0/XCK/PCINT20)_2") (pintype "bidirectional"))
      (node (ref "OLED2") (pin "3") (pinfunction "3_3") (pintype "passive"))
    )
    (net (code "67") (name "OLED_DC") (class "Default")
      (node (ref "IC2") (pin "11") (pinfunction "PD7(AIN1/PCINT23)_11") (pintype "bidirectional"))
      (node (ref "OLED2") (pin "4") (pinfunction "4_4") (pintype "passive"))
    )
    (net (code "68") (name "RESET") (class "Default")
      (node (ref "IC2") (pin "29") (pinfunction "PC6(/RESET/PCINT14)_29") (pintype "bidirectional"))
      (node (ref "JP1") (pin "2") (pinfunction "2_2") (pintype "passive"))
      (node (ref "JP2") (pin "3") (pinfunction "3_3") (pintype "passive"))
      (node (ref "R20") (pin "1") (pinfunction "1_1") (pintype "passive"))
      (node (ref "T6002") (pin "P$3") (pinfunction "2_P$3") (pintype "passive"))
      (node (ref "T6002") (pin "P$4") (pinfunction "2_P$4") (pintype "passive"))
      (node (ref "U$5") (pin "RST") (pinfunction "P$3_RST") (pintype "bidirectional"))
    )
    (net (code "69") (name "RX") (class "Default")
      (node (ref "IC2") (pin "30") (pinfunction "PD0(RXD/PCINT16)_30") (pintype "bidirectional"))
      (node (ref "IC3") (pin "1") (pinfunction "TXD_1") (pintype "output"))
    )
    (net (code "70") (name "SCK") (class "Default")
      (node (ref "IC2") (pin "17") (pinfunction "PB5(SCK/PCINT5)_17") (pintype "bidirectional"))
      (node (ref "OLED2") (pin "1") (pinfunction "1_1") (pintype "passive"))
      (node (ref "U$5") (pin "SCK") (pinfunction "P$2_SCK") (pintype "bidirectional"))
    )
    (net (code "71") (name "SCL_MC") (class "Default")
      (node (ref "I2C2") (pin "2") (pinfunction "2_2") (pintype "passive"))
      (node (ref "IC2") (pin "28") (pinfunction "PC5(ADC5/SCL/PCINT13)_28") (pintype "bidirectional"))
    )
    (net (code "72") (name "SCL_PWR") (class "Default")
      (node (ref "I2C1") (pin "2") (pinfunction "2_2") (pintype "passive"))
      (node (ref "R7") (pin "1") (pinfunction "1_1") (pintype "passive"))
      (node (ref "U1") (pin "10") (pinfunction "SCL_10") (pintype "bidirectional"))
      (node (ref "U2") (pin "4") (pinfunction "SCL_4") (pintype "input"))
    )
    (net (code "73") (name "SDA_MC") (class "Default")
      (node (ref "I2C2") (pin "3") (pinfunction "3_3") (pintype "passive"))
      (node (ref "IC2") (pin "27") (pinfunction "PC4(ADC4/SDA/PCINT12)_27") (pintype "bidirectional"))
    )
    (net (code "74") (name "SDA_PWR") (class "Default")
      (node (ref "I2C1") (pin "3") (pinfunction "3_3") (pintype "passive"))
      (node (ref "R6") (pin "1") (pinfunction "1_1") (pintype "passive"))
      (node (ref "U1") (pin "9") (pinfunction "SDA_9") (pintype "bidirectional"))
      (node (ref "U2") (pin "6") (pinfunction "SDA_6") (pintype "bidirectional"))
    )
    (net (code "75") (name "TC_1_N") (class "Default")
      (node (ref "C5") (pin "2") (pinfunction "2_2") (pintype "passive"))
      (node (ref "D9") (pin "1") (pinfunction "A1_1") (pintype "passive"))
      (node (ref "D9") (pin "2") (pinfunction "C2_2") (pintype "passive"))
      (node (ref "R9") (pin "1") (pinfunction "1_1") (pintype "passive"))
      (node (ref "U$2") (pin "P$1") (pinfunction "P$1_P$1") (pintype "bidirectional"))
      (node (ref "U1") (pin "5") (pinfunction "AIN1_5") (pintype "bidirectional"))
    )
    (net (code "76") (name "TC_1_P") (class "Default")
      (node (ref "C5") (pin "1") (pinfunction "1_1") (pintype "passive"))
      (node (ref "D9") (pin "3") (pinfunction "C1A2_3") (pintype "passive"))
      (node (ref "R18") (pin "2") (pinfunction "2_2") (pintype "passive"))
      (node (ref "U1") (pin "4") (pinfunction "AIN0_4") (pintype "bidirectional"))
    )
    (net (code "77") (name "TC_2_N") (class "Default")
      (node (ref "C4") (pin "2") (pinfunction "2_2") (pintype "passive"))
      (node (ref "D8") (pin "1") (pinfunction "A1_1") (pintype "passive"))
      (node (ref "D8") (pin "2") (pinfunction "C2_2") (pintype "passive"))
      (node (ref "R8") (pin "1") (pinfunction "1_1") (pintype "passive"))
      (node (ref "U$3") (pin "P$1") (pinfunction "P$1_P$1") (pintype "bidirectional"))
      (node (ref "U1") (pin "7") (pinfunction "AIN3_7") (pintype "bidirectional"))
    )
    (net (code "78") (name "TC_2_P") (class "Default")
      (node (ref "C4") (pin "1") (pinfunction "1_1") (pintype "passive"))
      (node (ref "D8") (pin "3") (pinfunction "C1A2_3") (pintype "passive"))
      (node (ref "R17") (pin "2") (pinfunction "2_2") (pintype "passive"))
      (node (ref "U1") (pin "6") (pinfunction "AIN2_6") (pintype "bidirectional"))
    )
    (net (code "79") (name "TX") (class "Default")
      (node (ref "IC2") (pin "31") (pinfunction "PD1(TXD/PCINT17)_31") (pintype "bidirectional"))
      (node (ref "IC3") (pin "5") (pinfunction "RXD_5") (pintype "input"))
    )
    (net (code "80") (name "USB+") (class "Default")
      (node (ref "IC3") (pin "15") (pinfunction "USBDP_15") (pintype "bidirectional"))
      (node (ref "USB") (pin "D+") (pinfunction "D+_D+") (pintype "bidirectional"))
    )
    (net (code "81") (name "USB-") (class "Default")
      (node (ref "IC3") (pin "16") (pinfunction "USBDM_16") (pintype "bidirectional"))
      (node (ref "USB") (pin "D-") (pinfunction "D-_D-") (pintype "bidirectional"))
    )
    (net (code "82") (name "V_USB") (class "Default")
      (node (ref "D2") (pin "A") (pinfunction "A_A") (pintype "passive"))
      (node (ref "F2") (pin "2") (pinfunction "2_2") (pintype "passive"))
    )
    (net (code "83") (name "ZC_MC") (class "Default")
      (node (ref "IC2") (pin "32") (pinfunction "PD2(INT0/PCINT18)_32") (pintype "bidirectional"))
      (node (ref "SIG2") (pin "2") (pinfunction "2_2") (pintype "passive"))
    )
    (net (code "84") (name "ZC_PWR") (class "Default")
      (node (ref "OK1") (pin "4") (pinfunction "C_4") (pintype "passive"))
      (node (ref "R12") (pin "2") (pinfunction "2_2") (pintype "passive"))
      (node (ref "SIG1") (pin "2") (pinfunction "2_2") (pintype "passive"))
    )
    (net (code "85") (name "unconnected-(IC3-CBUS2-Pad13)") (class "Default")
      (node (ref "IC3") (pin "13") (pinfunction "CBUS2_13") (pintype "bidirectional"))
    )
    (net (code "86") (name "unconnected-(IC3-CBUS3-Pad14)") (class "Default")
      (node (ref "IC3") (pin "14") (pinfunction "CBUS3_14") (pintype "bidirectional"))
    )
    (net (code "87") (name "unconnected-(IC3-CBUS4-Pad12)") (class "Default")
      (node (ref "IC3") (pin "12") (pinfunction "CBUS4_12") (pintype "bidirectional"))
    )
    (net (code "88") (name "unconnected-(IC3-OSCI-Pad27)") (class "Default")
      (node (ref "IC3") (pin "27") (pinfunction "OSCI_27") (pintype "input"))
    )
    (net (code "89") (name "unconnected-(IC3-OSCO-Pad28)") (class "Default")
      (node (ref "IC3") (pin "28") (pinfunction "OSCO_28") (pintype "output"))
    )
    (net (code "90") (name "unconnected-(IC3-~{CTS}-Pad11)") (class "Default")
      (node (ref "IC3") (pin "11") (pinfunction "~{CTS}_11") (pintype "input"))
    )
    (net (code "91") (name "unconnected-(IC3-~{DCD}-Pad10)") (class "Default")
      (node (ref "IC3") (pin "10") (pinfunction "~{DCD}_10") (pintype "input"))
    )
    (net (code "92") (name "unconnected-(IC3-~{DSR}-Pad9)") (class "Default")
      (node (ref "IC3") (pin "9") (pinfunction "~{DSR}_9") (pintype "input"))
    )
    (net (code "93") (name "unconnected-(IC3-~{RESET}-Pad19)") (class "Default")
      (node (ref "IC3") (pin "19") (pinfunction "~{RESET}_19") (pintype "input"))
    )
    (net (code "94") (name "unconnected-(IC3-~{RI}-Pad6)") (class "Default")
      (node (ref "IC3") (pin "6") (pinfunction "~{RI}_6") (pintype "input"))
    )
    (net (code "95") (name "unconnected-(IC3-~{RTS}-Pad3)") (class "Default")
      (node (ref "IC3") (pin "3") (pinfunction "~{RTS}_3") (pintype "output"))
    )
    (net (code "96") (name "unconnected-(JP2-Pad1)") (class "Default")
      (node (ref "JP2") (pin "1") (pinfunction "1_1") (pintype "passive"))
    )
    (net (code "97") (name "unconnected-(U2-ADDR-Pad1)") (class "Default")
      (node (ref "U2") (pin "1") (pinfunction "ADDR_1") (pintype "input"))
    )
    (net (code "98") (name "unconnected-(USB-PadID)") (class "Default")
      (node (ref "USB") (pin "ID") (pinfunction "ID_ID") (pintype "bidirectional"))
    )
  )
)
